# AquaBot_Stock_Controller.net
KiCad netlist of a schematic drawn in Altium Designer
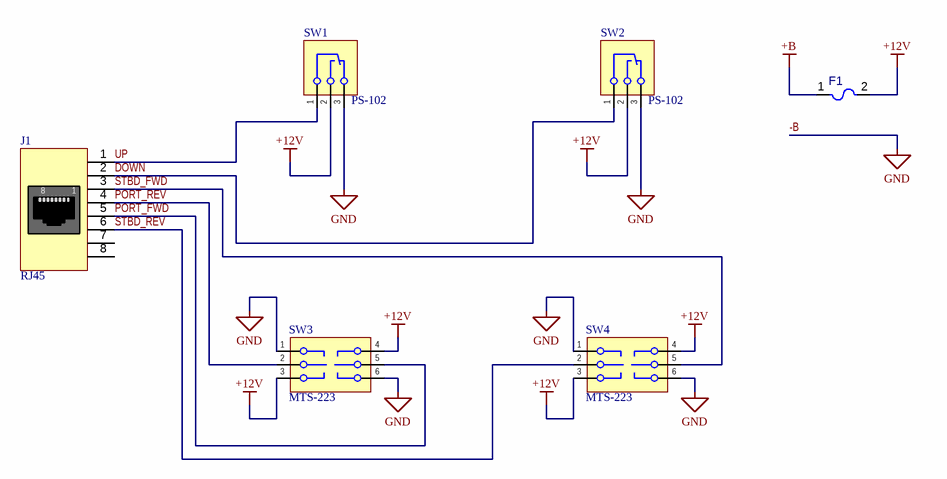
[diagram p0: AquaBot Stock Controller.SchDoc]

(export (version "E")
  (design (tool "Eeschema 10.0.6"))
  (components
    (comp (ref "F1")
      (value "Automotive Micro Fuse Holder")
      (footprint "Automotive Micro Fuse Holder-Footprint-1")
      (description "PTH fuse holder")
      (libsource (lib "Scion Research") (part "FUSE-2"))
    )
    (comp (ref "J1")
      (value "RJ45")
      (footprint "RJ45-Footprint-1")
      (libsource (lib "Scion Research") (part "RJ45-Symbol-1"))
    )
    (comp (ref "SW1")
      (value "PS-102")
      (footprint "PS-102-Footprint-RA")
      (description "Momentary push button std 6mm mounting")
      (libsource (lib "Scion Research") (part "PS-102-Symbol-1"))
    )
    (comp (ref "SW2")
      (value "PS-102")
      (footprint "PS-102-Footprint-RA")
      (description "Momentary push button std 6mm mounting")
      (libsource (lib "Scion Research") (part "PS-102-Symbol-1"))
    )
    (comp (ref "SW3")
      (value "MTS-223")
      (footprint "MTS-223-Footprint-1")
      (description "On Off On momentary toggle switch DPDT")
      (libsource (lib "Scion Research") (part "MTS-223-Symbol-1"))
    )
    (comp (ref "SW4")
      (value "MTS-223")
      (footprint "MTS-223-Footprint-1")
      (description "On Off On momentary toggle switch DPDT")
      (libsource (lib "Scion Research") (part "MTS-223-Symbol-1"))
    )
  )
  (nets
    (net (code "1") (name "+12V") (class "Default")
      (node (ref "F1") (pin "2") (pinfunction "2_2") (pintype "passive"))
      (node (ref "SW1") (pin "2") (pinfunction "NO_2") (pintype "passive"))
      (node (ref "SW2") (pin "2") (pinfunction "NO_2") (pintype "passive"))
      (node (ref "SW3") (pin "3") (pinfunction "NO_1B_3") (pintype "passive"))
      (node (ref "SW3") (pin "4") (pinfunction "NO_2A_4") (pintype "passive"))
      (node (ref "SW4") (pin "3") (pinfunction "NO_1B_3") (pintype "passive"))
      (node (ref "SW4") (pin "4") (pinfunction "NO_2A_4") (pintype "passive"))
    )
    (net (code "2") (name "+B") (class "Default")
      (node (ref "F1") (pin "1") (pinfunction "1_1") (pintype "passive"))
    )
    (net (code "3") (name "/DOWN") (class "Default")
      (node (ref "J1") (pin "2") (pinfunction "2_2") (pintype "passive"))
      (node (ref "SW2") (pin "1") (pinfunction "C_1") (pintype "passive"))
    )
    (net (code "4") (name "/PORT_FWD") (class "Default")
      (node (ref "J1") (pin "5") (pinfunction "5_5") (pintype "passive"))
      (node (ref "SW3") (pin "5") (pinfunction "C_2_5") (pintype "passive"))
    )
    (net (code "5") (name "/PORT_REV") (class "Default")
      (node (ref "J1") (pin "4") (pinfunction "4_4") (pintype "passive"))
      (node (ref "SW3") (pin "2") (pinfunction "C_1_2") (pintype "passive"))
    )
    (net (code "6") (name "/STBD_FWD") (class "Default")
      (node (ref "J1") (pin "3") (pinfunction "3_3") (pintype "passive"))
      (node (ref "SW4") (pin "5") (pinfunction "C_2_5") (pintype "passive"))
    )
    (net (code "7") (name "/STBD_REV") (class "Default")
      (node (ref "J1") (pin "6") (pinfunction "6_6") (pintype "passive"))
      (node (ref "SW4") (pin "2") (pinfunction "C_1_2") (pintype "passive"))
    )
    (net (code "8") (name "/UP") (class "Default")
      (node (ref "J1") (pin "1") (pinfunction "1_1") (pintype "passive"))
      (node (ref "SW1") (pin "1") (pinfunction "C_1") (pintype "passive"))
    )
    (net (code "9") (name "GND") (class "Default")
      (node (ref "SW1") (pin "3") (pinfunction "NC_3") (pintype "passive"))
      (node (ref "SW2") (pin "3") (pinfunction "NC_3") (pintype "passive"))
      (node (ref "SW3") (pin "1") (pinfunction "NO_1A_1") (pintype "passive"))
      (node (ref "SW3") (pin "6") (pinfunction "NO_2B_6") (pintype "passive"))
      (node (ref "SW4") (pin "1") (pinfunction "NO_1A_1") (pintype "passive"))
      (node (ref "SW4") (pin "6") (pinfunction "NO_2B_6") (pintype "passive"))
    )
    (net (code "10") (name "unconnected-(J1-Pad7)") (class "Default")
      (node (ref "J1") (pin "7") (pinfunction "7_7") (pintype "passive"))
    )
    (net (code "11") (name "unconnected-(J1-Pad8)") (class "Default")
      (node (ref "J1") (pin "8") (pinfunction "8_8") (pintype "passive"))
    )
  )
)
